# PCB-BI8-1x8S.net
KiCad netlist of a schematic drawn in EAGLE
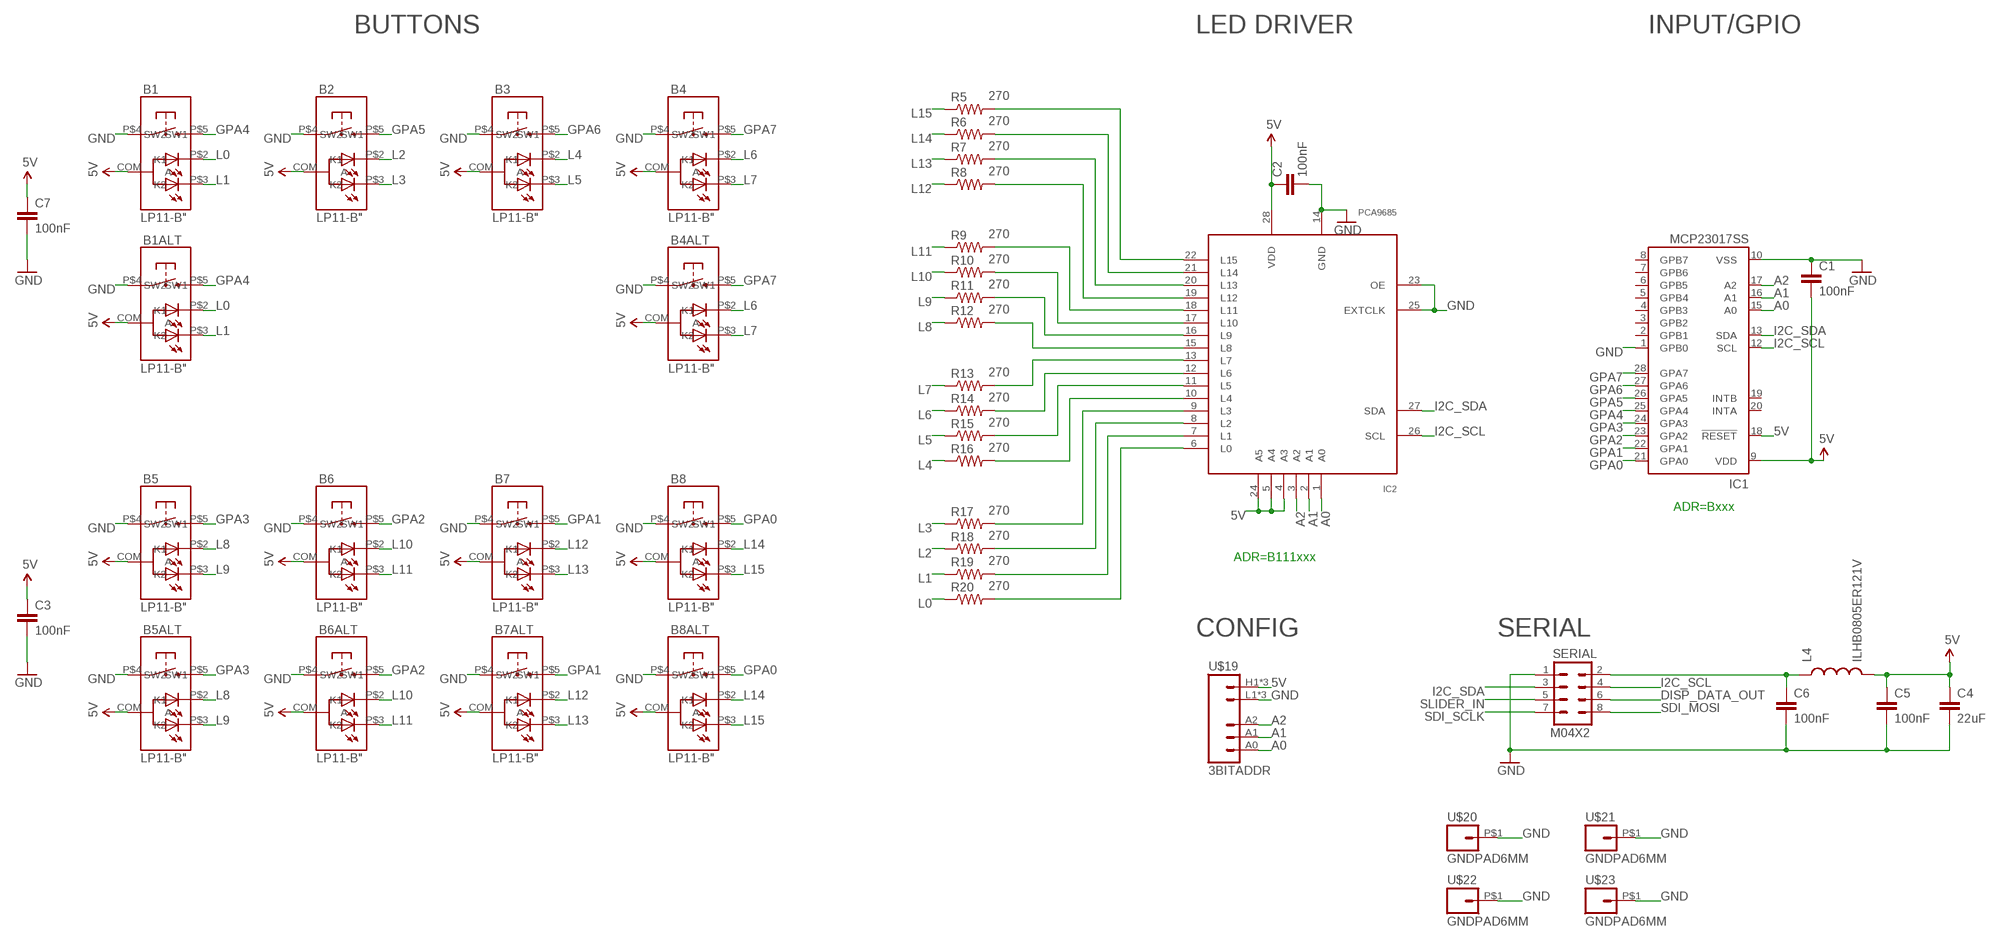
[diagram p0: schematic, sheet 1]

(export (version "E")
  (design (tool "Eeschema 10.0.6"))
  (components
    (comp (ref "B1")
      (value "LP11-B\"")
      (footprint "eagle-import:LP11")
      (libsource (lib "eagle-import") (part "LP11-B{dblquote}"))
    )
    (comp (ref "B1ALT")
      (value "LP11-B\"")
      (footprint "eagle-import:LP11")
      (libsource (lib "eagle-import") (part "LP11-B{dblquote}"))
    )
    (comp (ref "B2")
      (value "LP11-B\"")
      (footprint "eagle-import:LP11")
      (libsource (lib "eagle-import") (part "LP11-B{dblquote}"))
    )
    (comp (ref "B3")
      (value "LP11-B\"")
      (footprint "eagle-import:LP11")
      (libsource (lib "eagle-import") (part "LP11-B{dblquote}"))
    )
    (comp (ref "B4")
      (value "LP11-B\"")
      (footprint "eagle-import:LP11")
      (libsource (lib "eagle-import") (part "LP11-B{dblquote}"))
    )
    (comp (ref "B4ALT")
      (value "LP11-B\"")
      (footprint "eagle-import:LP11")
      (libsource (lib "eagle-import") (part "LP11-B{dblquote}"))
    )
    (comp (ref "B5")
      (value "LP11-B\"")
      (footprint "eagle-import:LP11")
      (libsource (lib "eagle-import") (part "LP11-B{dblquote}"))
    )
    (comp (ref "B5ALT")
      (value "LP11-B\"")
      (footprint "eagle-import:LP11")
      (libsource (lib "eagle-import") (part "LP11-B{dblquote}"))
    )
    (comp (ref "B6")
      (value "LP11-B\"")
      (footprint "eagle-import:LP11")
      (libsource (lib "eagle-import") (part "LP11-B{dblquote}"))
    )
    (comp (ref "B6ALT")
      (value "LP11-B\"")
      (footprint "eagle-import:LP11")
      (libsource (lib "eagle-import") (part "LP11-B{dblquote}"))
    )
    (comp (ref "B7")
      (value "LP11-B\"")
      (footprint "eagle-import:LP11")
      (libsource (lib "eagle-import") (part "LP11-B{dblquote}"))
    )
    (comp (ref "B7ALT")
      (value "LP11-B\"")
      (footprint "eagle-import:LP11")
      (libsource (lib "eagle-import") (part "LP11-B{dblquote}"))
    )
    (comp (ref "B8")
      (value "LP11-B\"")
      (footprint "eagle-import:LP11")
      (libsource (lib "eagle-import") (part "LP11-B{dblquote}"))
    )
    (comp (ref "B8ALT")
      (value "LP11-B\"")
      (footprint "eagle-import:LP11")
      (libsource (lib "eagle-import") (part "LP11-B{dblquote}"))
    )
    (comp (ref "C1")
      (value "100nF")
      (footprint "eagle-import:0603-CAP")
      (libsource (lib "eagle-import") (part "CAP0603-CAP"))
    )
    (comp (ref "C2")
      (value "100nF")
      (footprint "eagle-import:0603-CAP")
      (libsource (lib "eagle-import") (part "CAP0603-CAP"))
    )
    (comp (ref "C3")
      (value "100nF")
      (footprint "eagle-import:0603-CAP")
      (libsource (lib "eagle-import") (part "CAP0603-CAP"))
    )
    (comp (ref "C4")
      (value "22uF")
      (footprint "eagle-import:0805")
      (libsource (lib "eagle-import") (part "CAP0805"))
    )
    (comp (ref "C5")
      (value "100nF")
      (footprint "eagle-import:0603-CAP")
      (libsource (lib "eagle-import") (part "CAP0603-CAP"))
    )
    (comp (ref "C6")
      (value "100nF")
      (footprint "eagle-import:0603-CAP")
      (libsource (lib "eagle-import") (part "CAP0603-CAP"))
    )
    (comp (ref "C7")
      (value "100nF")
      (footprint "eagle-import:0603-CAP")
      (libsource (lib "eagle-import") (part "CAP0603-CAP"))
    )
    (comp (ref "IC1")
      (value "MCP23017SS")
      (footprint "eagle-import:SSOP28")
      (fields
        (field (name "MF") "MICROCHIP")
        (field (name "MPN") "MCP23017-E/SS")
        (field (name "MPN_1") "MCP23017-E/SS")
        (field (name "OC_FARNELL") "1467674")
        (field (name "OC_NEWARK") "31K2960")
      )
      (libsource (lib "eagle-import") (part "MCP23017SS"))
    )
    (comp (ref "IC2")
      (value "PCA9685")
      (footprint "eagle-import:TSSOP28")
      (libsource (lib "eagle-import") (part "PCA9685"))
    )
    (comp (ref "L4")
      (value "ILHB0805ER121V")
      (footprint "eagle-import:0805")
      (libsource (lib "eagle-import") (part "INDUCTOR0805"))
    )
    (comp (ref "R5")
      (value "270")
      (footprint "eagle-import:0603-RES")
      (libsource (lib "eagle-import") (part "RESISTOR0603-RES"))
    )
    (comp (ref "R6")
      (value "270")
      (footprint "eagle-import:0603-RES")
      (libsource (lib "eagle-import") (part "RESISTOR0603-RES"))
    )
    (comp (ref "R7")
      (value "270")
      (footprint "eagle-import:0603-RES")
      (libsource (lib "eagle-import") (part "RESISTOR0603-RES"))
    )
    (comp (ref "R8")
      (value "270")
      (footprint "eagle-import:0603-RES")
      (libsource (lib "eagle-import") (part "RESISTOR0603-RES"))
    )
    (comp (ref "R9")
      (value "270")
      (footprint "eagle-import:0603-RES")
      (libsource (lib "eagle-import") (part "RESISTOR0603-RES"))
    )
    (comp (ref "R10")
      (value "270")
      (footprint "eagle-import:0603-RES")
      (libsource (lib "eagle-import") (part "RESISTOR0603-RES"))
    )
    (comp (ref "R11")
      (value "270")
      (footprint "eagle-import:0603-RES")
      (libsource (lib "eagle-import") (part "RESISTOR0603-RES"))
    )
    (comp (ref "R12")
      (value "270")
      (footprint "eagle-import:0603-RES")
      (libsource (lib "eagle-import") (part "RESISTOR0603-RES"))
    )
    (comp (ref "R13")
      (value "270")
      (footprint "eagle-import:0603-RES")
      (libsource (lib "eagle-import") (part "RESISTOR0603-RES"))
    )
    (comp (ref "R14")
      (value "270")
      (footprint "eagle-import:0603-RES")
      (libsource (lib "eagle-import") (part "RESISTOR0603-RES"))
    )
    (comp (ref "R15")
      (value "270")
      (footprint "eagle-import:0603-RES")
      (libsource (lib "eagle-import") (part "RESISTOR0603-RES"))
    )
    (comp (ref "R16")
      (value "270")
      (footprint "eagle-import:0603-RES")
      (libsource (lib "eagle-import") (part "RESISTOR0603-RES"))
    )
    (comp (ref "R17")
      (value "270")
      (footprint "eagle-import:0603-RES")
      (libsource (lib "eagle-import") (part "RESISTOR0603-RES"))
    )
    (comp (ref "R18")
      (value "270")
      (footprint "eagle-import:0603-RES")
      (libsource (lib "eagle-import") (part "RESISTOR0603-RES"))
    )
    (comp (ref "R19")
      (value "270")
      (footprint "eagle-import:0603-RES")
      (libsource (lib "eagle-import") (part "RESISTOR0603-RES"))
    )
    (comp (ref "R20")
      (value "270")
      (footprint "eagle-import:0603-RES")
      (libsource (lib "eagle-import") (part "RESISTOR0603-RES"))
    )
    (comp (ref "SERIAL")
      (value "M04X2")
      (footprint "eagle-import:2X4")
      (libsource (lib "eagle-import") (part "M04X2"))
    )
    (comp (ref "U$19")
      (value "3BITADDR")
      (footprint "eagle-import:3BITADDR")
      (libsource (lib "eagle-import") (part "3BITADDR"))
    )
    (comp (ref "U$20")
      (value "GNDPAD6MM")
      (footprint "eagle-import:3.2MMPAD6MM")
      (libsource (lib "eagle-import") (part "GNDPAD6MM"))
    )
    (comp (ref "U$21")
      (value "GNDPAD6MM")
      (footprint "eagle-import:3.2MMPAD6MM")
      (libsource (lib "eagle-import") (part "GNDPAD6MM"))
    )
    (comp (ref "U$22")
      (value "GNDPAD6MM")
      (footprint "eagle-import:3.2MMPAD6MM")
      (libsource (lib "eagle-import") (part "GNDPAD6MM"))
    )
    (comp (ref "U$23")
      (value "GNDPAD6MM")
      (footprint "eagle-import:3.2MMPAD6MM")
      (libsource (lib "eagle-import") (part "GNDPAD6MM"))
    )
  )
  (nets
    (net (code "1") (name "/A0") (class "Default")
      (node (ref "IC1") (pin "15") (pinfunction "A0_15") (pintype "input"))
      (node (ref "IC2") (pin "1") (pinfunction "A0_1") (pintype "input"))
      (node (ref "U$19") (pin "A0") (pinfunction "A0_A0") (pintype "passive"))
    )
    (net (code "2") (name "/A1") (class "Default")
      (node (ref "IC1") (pin "16") (pinfunction "A1_16") (pintype "input"))
      (node (ref "IC2") (pin "2") (pinfunction "A1_2") (pintype "input"))
      (node (ref "U$19") (pin "A1") (pinfunction "A1_A1") (pintype "passive"))
    )
    (net (code "3") (name "/A2") (class "Default")
      (node (ref "IC1") (pin "17") (pinfunction "A2_17") (pintype "input"))
      (node (ref "IC2") (pin "3") (pinfunction "A2_3") (pintype "input"))
      (node (ref "U$19") (pin "A2") (pinfunction "A2_A2") (pintype "passive"))
    )
    (net (code "4") (name "/DISP_DATA_OUT") (class "Default")
      (node (ref "SERIAL") (pin "6") (pinfunction "6_6") (pintype "passive"))
    )
    (net (code "5") (name "/GPA0") (class "Default")
      (node (ref "B8") (pin "P$5") (pinfunction "SW2_P$5") (pintype "bidirectional"))
      (node (ref "B8ALT") (pin "P$5") (pinfunction "SW2_P$5") (pintype "bidirectional"))
      (node (ref "IC1") (pin "21") (pinfunction "GPA0_21") (pintype "bidirectional"))
    )
    (net (code "6") (name "/GPA1") (class "Default")
      (node (ref "B7") (pin "P$5") (pinfunction "SW2_P$5") (pintype "bidirectional"))
      (node (ref "B7ALT") (pin "P$5") (pinfunction "SW2_P$5") (pintype "bidirectional"))
      (node (ref "IC1") (pin "22") (pinfunction "GPA1_22") (pintype "bidirectional"))
    )
    (net (code "7") (name "/GPA2") (class "Default")
      (node (ref "B6") (pin "P$5") (pinfunction "SW2_P$5") (pintype "bidirectional"))
      (node (ref "B6ALT") (pin "P$5") (pinfunction "SW2_P$5") (pintype "bidirectional"))
      (node (ref "IC1") (pin "23") (pinfunction "GPA2_23") (pintype "bidirectional"))
    )
    (net (code "8") (name "/GPA3") (class "Default")
      (node (ref "B5") (pin "P$5") (pinfunction "SW2_P$5") (pintype "bidirectional"))
      (node (ref "B5ALT") (pin "P$5") (pinfunction "SW2_P$5") (pintype "bidirectional"))
      (node (ref "IC1") (pin "24") (pinfunction "GPA3_24") (pintype "bidirectional"))
    )
    (net (code "9") (name "/GPA4") (class "Default")
      (node (ref "B1") (pin "P$5") (pinfunction "SW2_P$5") (pintype "bidirectional"))
      (node (ref "B1ALT") (pin "P$5") (pinfunction "SW2_P$5") (pintype "bidirectional"))
      (node (ref "IC1") (pin "25") (pinfunction "GPA4_25") (pintype "bidirectional"))
    )
    (net (code "10") (name "/GPA5") (class "Default")
      (node (ref "B2") (pin "P$5") (pinfunction "SW2_P$5") (pintype "bidirectional"))
      (node (ref "IC1") (pin "26") (pinfunction "GPA5_26") (pintype "bidirectional"))
    )
    (net (code "11") (name "/GPA6") (class "Default")
      (node (ref "B3") (pin "P$5") (pinfunction "SW2_P$5") (pintype "bidirectional"))
      (node (ref "IC1") (pin "27") (pinfunction "GPA6_27") (pintype "bidirectional"))
    )
    (net (code "12") (name "/GPA7") (class "Default")
      (node (ref "B4") (pin "P$5") (pinfunction "SW2_P$5") (pintype "bidirectional"))
      (node (ref "B4ALT") (pin "P$5") (pinfunction "SW2_P$5") (pintype "bidirectional"))
      (node (ref "IC1") (pin "28") (pinfunction "GPA7_28") (pintype "bidirectional"))
    )
    (net (code "13") (name "/I2C_SCL") (class "Default")
      (node (ref "IC1") (pin "12") (pinfunction "SCL_12") (pintype "input"))
      (node (ref "IC2") (pin "26") (pinfunction "SCL_26") (pintype "input"))
      (node (ref "SERIAL") (pin "4") (pinfunction "4_4") (pintype "passive"))
    )
    (net (code "14") (name "/I2C_SDA") (class "Default")
      (node (ref "IC1") (pin "13") (pinfunction "SDA_13") (pintype "bidirectional"))
      (node (ref "IC2") (pin "27") (pinfunction "SDA_27") (pintype "input"))
      (node (ref "SERIAL") (pin "3") (pinfunction "3_3") (pintype "passive"))
    )
    (net (code "15") (name "/L0") (class "Default")
      (node (ref "B1") (pin "P$2") (pinfunction "K1_P$2") (pintype "bidirectional"))
      (node (ref "B1ALT") (pin "P$2") (pinfunction "K1_P$2") (pintype "bidirectional"))
      (node (ref "R20") (pin "1") (pinfunction "1_1") (pintype "passive"))
    )
    (net (code "16") (name "/L1") (class "Default")
      (node (ref "B1") (pin "P$3") (pinfunction "K2_P$3") (pintype "bidirectional"))
      (node (ref "B1ALT") (pin "P$3") (pinfunction "K2_P$3") (pintype "bidirectional"))
      (node (ref "R19") (pin "1") (pinfunction "1_1") (pintype "passive"))
    )
    (net (code "17") (name "/L2") (class "Default")
      (node (ref "B2") (pin "P$2") (pinfunction "K1_P$2") (pintype "bidirectional"))
      (node (ref "R18") (pin "1") (pinfunction "1_1") (pintype "passive"))
    )
    (net (code "18") (name "/L3") (class "Default")
      (node (ref "B2") (pin "P$3") (pinfunction "K2_P$3") (pintype "bidirectional"))
      (node (ref "R17") (pin "1") (pinfunction "1_1") (pintype "passive"))
    )
    (net (code "19") (name "/L4") (class "Default")
      (node (ref "B3") (pin "P$2") (pinfunction "K1_P$2") (pintype "bidirectional"))
      (node (ref "R16") (pin "1") (pinfunction "1_1") (pintype "passive"))
    )
    (net (code "20") (name "/L5") (class "Default")
      (node (ref "B3") (pin "P$3") (pinfunction "K2_P$3") (pintype "bidirectional"))
      (node (ref "R15") (pin "1") (pinfunction "1_1") (pintype "passive"))
    )
    (net (code "21") (name "/L6") (class "Default")
      (node (ref "B4") (pin "P$2") (pinfunction "K1_P$2") (pintype "bidirectional"))
      (node (ref "B4ALT") (pin "P$2") (pinfunction "K1_P$2") (pintype "bidirectional"))
      (node (ref "R14") (pin "1") (pinfunction "1_1") (pintype "passive"))
    )
    (net (code "22") (name "/L7") (class "Default")
      (node (ref "B4") (pin "P$3") (pinfunction "K2_P$3") (pintype "bidirectional"))
      (node (ref "B4ALT") (pin "P$3") (pinfunction "K2_P$3") (pintype "bidirectional"))
      (node (ref "R13") (pin "1") (pinfunction "1_1") (pintype "passive"))
    )
    (net (code "23") (name "/L8") (class "Default")
      (node (ref "B5") (pin "P$2") (pinfunction "K1_P$2") (pintype "bidirectional"))
      (node (ref "B5ALT") (pin "P$2") (pinfunction "K1_P$2") (pintype "bidirectional"))
      (node (ref "R12") (pin "1") (pinfunction "1_1") (pintype "passive"))
    )
    (net (code "24") (name "/L9") (class "Default")
      (node (ref "B5") (pin "P$3") (pinfunction "K2_P$3") (pintype "bidirectional"))
      (node (ref "B5ALT") (pin "P$3") (pinfunction "K2_P$3") (pintype "bidirectional"))
      (node (ref "R11") (pin "1") (pinfunction "1_1") (pintype "passive"))
    )
    (net (code "25") (name "/L10") (class "Default")
      (node (ref "B6") (pin "P$2") (pinfunction "K1_P$2") (pintype "bidirectional"))
      (node (ref "B6ALT") (pin "P$2") (pinfunction "K1_P$2") (pintype "bidirectional"))
      (node (ref "R10") (pin "1") (pinfunction "1_1") (pintype "passive"))
    )
    (net (code "26") (name "/L11") (class "Default")
      (node (ref "B6") (pin "P$3") (pinfunction "K2_P$3") (pintype "bidirectional"))
      (node (ref "B6ALT") (pin "P$3") (pinfunction "K2_P$3") (pintype "bidirectional"))
      (node (ref "R9") (pin "1") (pinfunction "1_1") (pintype "passive"))
    )
    (net (code "27") (name "/L12") (class "Default")
      (node (ref "B7") (pin "P$2") (pinfunction "K1_P$2") (pintype "bidirectional"))
      (node (ref "B7ALT") (pin "P$2") (pinfunction "K1_P$2") (pintype "bidirectional"))
      (node (ref "R8") (pin "1") (pinfunction "1_1") (pintype "passive"))
    )
    (net (code "28") (name "/L13") (class "Default")
      (node (ref "B7") (pin "P$3") (pinfunction "K2_P$3") (pintype "bidirectional"))
      (node (ref "B7ALT") (pin "P$3") (pinfunction "K2_P$3") (pintype "bidirectional"))
      (node (ref "R7") (pin "1") (pinfunction "1_1") (pintype "passive"))
    )
    (net (code "29") (name "/L14") (class "Default")
      (node (ref "B8") (pin "P$2") (pinfunction "K1_P$2") (pintype "bidirectional"))
      (node (ref "B8ALT") (pin "P$2") (pinfunction "K1_P$2") (pintype "bidirectional"))
      (node (ref "R6") (pin "1") (pinfunction "1_1") (pintype "passive"))
    )
    (net (code "30") (name "/L15") (class "Default")
      (node (ref "B8") (pin "P$3") (pinfunction "K2_P$3") (pintype "bidirectional"))
      (node (ref "B8ALT") (pin "P$3") (pinfunction "K2_P$3") (pintype "bidirectional"))
      (node (ref "R5") (pin "1") (pinfunction "1_1") (pintype "passive"))
    )
    (net (code "31") (name "/SDI_MOSI") (class "Default")
      (node (ref "SERIAL") (pin "8") (pinfunction "8_8") (pintype "passive"))
    )
    (net (code "32") (name "/SDI_SCLK") (class "Default")
      (node (ref "SERIAL") (pin "7") (pinfunction "7_7") (pintype "passive"))
    )
    (net (code "33") (name "/SLIDER_IN") (class "Default")
      (node (ref "SERIAL") (pin "5") (pinfunction "5_5") (pintype "passive"))
    )
    (net (code "34") (name "5V") (class "Default")
      (node (ref "B1") (pin "COM") (pinfunction "A_COM") (pintype "bidirectional"))
      (node (ref "B1ALT") (pin "COM") (pinfunction "A_COM") (pintype "bidirectional"))
      (node (ref "B2") (pin "COM") (pinfunction "A_COM") (pintype "bidirectional"))
      (node (ref "B3") (pin "COM") (pinfunction "A_COM") (pintype "bidirectional"))
      (node (ref "B4") (pin "COM") (pinfunction "A_COM") (pintype "bidirectional"))
      (node (ref "B4ALT") (pin "COM") (pinfunction "A_COM") (pintype "bidirectional"))
      (node (ref "B5") (pin "COM") (pinfunction "A_COM") (pintype "bidirectional"))
      (node (ref "B5ALT") (pin "COM") (pinfunction "A_COM") (pintype "bidirectional"))
      (node (ref "B6") (pin "COM") (pinfunction "A_COM") (pintype "bidirectional"))
      (node (ref "B6ALT") (pin "COM") (pinfunction "A_COM") (pintype "bidirectional"))
      (node (ref "B7") (pin "COM") (pinfunction "A_COM") (pintype "bidirectional"))
      (node (ref "B7ALT") (pin "COM") (pinfunction "A_COM") (pintype "bidirectional"))
      (node (ref "B8") (pin "COM") (pinfunction "A_COM") (pintype "bidirectional"))
      (node (ref "B8ALT") (pin "COM") (pinfunction "A_COM") (pintype "bidirectional"))
      (node (ref "C1") (pin "2") (pinfunction "2_2") (pintype "passive"))
      (node (ref "C2") (pin "1") (pinfunction "1_1") (pintype "passive"))
      (node (ref "C3") (pin "1") (pinfunction "1_1") (pintype "passive"))
      (node (ref "C4") (pin "1") (pinfunction "1_1") (pintype "passive"))
      (node (ref "C5") (pin "1") (pinfunction "1_1") (pintype "passive"))
      (node (ref "C7") (pin "1") (pinfunction "1_1") (pintype "passive"))
      (node (ref "IC1") (pin "18") (pinfunction "~{RESET}_18") (pintype "input"))
      (node (ref "IC1") (pin "9") (pinfunction "VDD_9") (pintype "power_in"))
      (node (ref "IC2") (pin "24") (pinfunction "A5_24") (pintype "input"))
      (node (ref "IC2") (pin "28") (pinfunction "VDD_28") (pintype "power_in"))
      (node (ref "IC2") (pin "4") (pinfunction "A3_4") (pintype "input"))
      (node (ref "IC2") (pin "5") (pinfunction "A4_5") (pintype "input"))
      (node (ref "L4") (pin "2") (pinfunction "2_2") (pintype "passive"))
      (node (ref "U$19") (pin "H1") (pinfunction "VCC_H1") (pintype "passive"))
      (node (ref "U$19") (pin "H2") (pinfunction "VCC_H2") (pintype "passive"))
      (node (ref "U$19") (pin "H3") (pinfunction "VCC_H3") (pintype "passive"))
    )
    (net (code "35") (name "GND") (class "Default")
      (node (ref "B1") (pin "P$4") (pinfunction "SW1_P$4") (pintype "bidirectional"))
      (node (ref "B1ALT") (pin "P$4") (pinfunction "SW1_P$4") (pintype "bidirectional"))
      (node (ref "B2") (pin "P$4") (pinfunction "SW1_P$4") (pintype "bidirectional"))
      (node (ref "B3") (pin "P$4") (pinfunction "SW1_P$4") (pintype "bidirectional"))
      (node (ref "B4") (pin "P$4") (pinfunction "SW1_P$4") (pintype "bidirectional"))
      (node (ref "B4ALT") (pin "P$4") (pinfunction "SW1_P$4") (pintype "bidirectional"))
      (node (ref "B5") (pin "P$4") (pinfunction "SW1_P$4") (pintype "bidirectional"))
      (node (ref "B5ALT") (pin "P$4") (pinfunction "SW1_P$4") (pintype "bidirectional"))
      (node (ref "B6") (pin "P$4") (pinfunction "SW1_P$4") (pintype "bidirectional"))
      (node (ref "B6ALT") (pin "P$4") (pinfunction "SW1_P$4") (pintype "bidirectional"))
      (node (ref "B7") (pin "P$4") (pinfunction "SW1_P$4") (pintype "bidirectional"))
      (node (ref "B7ALT") (pin "P$4") (pinfunction "SW1_P$4") (pintype "bidirectional"))
      (node (ref "B8") (pin "P$4") (pinfunction "SW1_P$4") (pintype "bidirectional"))
      (node (ref "B8ALT") (pin "P$4") (pinfunction "SW1_P$4") (pintype "bidirectional"))
      (node (ref "C1") (pin "1") (pinfunction "1_1") (pintype "passive"))
      (node (ref "C2") (pin "2") (pinfunction "2_2") (pintype "passive"))
      (node (ref "C3") (pin "2") (pinfunction "2_2") (pintype "passive"))
      (node (ref "C4") (pin "2") (pinfunction "2_2") (pintype "passive"))
      (node (ref "C5") (pin "2") (pinfunction "2_2") (pintype "passive"))
      (node (ref "C6") (pin "2") (pinfunction "2_2") (pintype "passive"))
      (node (ref "C7") (pin "2") (pinfunction "2_2") (pintype "passive"))
      (node (ref "IC1") (pin "1") (pinfunction "GPB0_1") (pintype "bidirectional"))
      (node (ref "IC1") (pin "10") (pinfunction "VSS_10") (pintype "power_in"))
      (node (ref "IC2") (pin "14") (pinfunction "GND_14") (pintype "power_in"))
      (node (ref "IC2") (pin "23") (pinfunction "OE_23") (pintype "input"))
      (node (ref "IC2") (pin "25") (pinfunction "EXTCLK_25") (pintype "input"))
      (node (ref "SERIAL") (pin "1") (pinfunction "1_1") (pintype "passive"))
      (node (ref "U$19") (pin "L1") (pinfunction "GND_L1") (pintype "passive"))
      (node (ref "U$19") (pin "L2") (pinfunction "GND_L2") (pintype "passive"))
      (node (ref "U$19") (pin "L3") (pinfunction "GND_L3") (pintype "passive"))
      (node (ref "U$20") (pin "P$1") (pinfunction "1_P$1") (pintype "passive"))
      (node (ref "U$21") (pin "P$1") (pinfunction "1_P$1") (pintype "passive"))
      (node (ref "U$22") (pin "P$1") (pinfunction "1_P$1") (pintype "passive"))
      (node (ref "U$23") (pin "P$1") (pinfunction "1_P$1") (pintype "passive"))
    )
    (net (code "36") (name "Net-(C6-Pad1)") (class "Default")
      (node (ref "C6") (pin "1") (pinfunction "1_1") (pintype "passive"))
      (node (ref "L4") (pin "1") (pinfunction "1_1") (pintype "passive"))
      (node (ref "SERIAL") (pin "2") (pinfunction "2_2") (pintype "passive"))
    )
    (net (code "37") (name "Net-(IC2-L0)") (class "Default")
      (node (ref "IC2") (pin "6") (pinfunction "L0_6") (pintype "output"))
      (node (ref "R20") (pin "2") (pinfunction "2_2") (pintype "passive"))
    )
    (net (code "38") (name "Net-(IC2-L1)") (class "Default")
      (node (ref "IC2") (pin "7") (pinfunction "L1_7") (pintype "output"))
      (node (ref "R19") (pin "2") (pinfunction "2_2") (pintype "passive"))
    )
    (net (code "39") (name "Net-(IC2-L2)") (class "Default")
      (node (ref "IC2") (pin "8") (pinfunction "L2_8") (pintype "output"))
      (node (ref "R18") (pin "2") (pinfunction "2_2") (pintype "passive"))
    )
    (net (code "40") (name "Net-(IC2-L3)") (class "Default")
      (node (ref "IC2") (pin "9") (pinfunction "L3_9") (pintype "output"))
      (node (ref "R17") (pin "2") (pinfunction "2_2") (pintype "passive"))
    )
    (net (code "41") (name "Net-(IC2-L4)") (class "Default")
      (node (ref "IC2") (pin "10") (pinfunction "L4_10") (pintype "output"))
      (node (ref "R16") (pin "2") (pinfunction "2_2") (pintype "passive"))
    )
    (net (code "42") (name "Net-(IC2-L5)") (class "Default")
      (node (ref "IC2") (pin "11") (pinfunction "L5_11") (pintype "output"))
      (node (ref "R15") (pin "2") (pinfunction "2_2") (pintype "passive"))
    )
    (net (code "43") (name "Net-(IC2-L6)") (class "Default")
      (node (ref "IC2") (pin "12") (pinfunction "L6_12") (pintype "output"))
      (node (ref "R14") (pin "2") (pinfunction "2_2") (pintype "passive"))
    )
    (net (code "44") (name "Net-(IC2-L7)") (class "Default")
      (node (ref "IC2") (pin "13") (pinfunction "L7_13") (pintype "output"))
      (node (ref "R13") (pin "2") (pinfunction "2_2") (pintype "passive"))
    )
    (net (code "45") (name "Net-(IC2-L8)") (class "Default")
      (node (ref "IC2") (pin "15") (pinfunction "L8_15") (pintype "output"))
      (node (ref "R12") (pin "2") (pinfunction "2_2") (pintype "passive"))
    )
    (net (code "46") (name "Net-(IC2-L9)") (class "Default")
      (node (ref "IC2") (pin "16") (pinfunction "L9_16") (pintype "output"))
      (node (ref "R11") (pin "2") (pinfunction "2_2") (pintype "passive"))
    )
    (net (code "47") (name "Net-(IC2-L10)") (class "Default")
      (node (ref "IC2") (pin "17") (pinfunction "L10_17") (pintype "output"))
      (node (ref "R10") (pin "2") (pinfunction "2_2") (pintype "passive"))
    )
    (net (code "48") (name "Net-(IC2-L11)") (class "Default")
      (node (ref "IC2") (pin "18") (pinfunction "L11_18") (pintype "output"))
      (node (ref "R9") (pin "2") (pinfunction "2_2") (pintype "passive"))
    )
    (net (code "49") (name "Net-(IC2-L12)") (class "Default")
      (node (ref "IC2") (pin "19") (pinfunction "L12_19") (pintype "output"))
      (node (ref "R8") (pin "2") (pinfunction "2_2") (pintype "passive"))
    )
    (net (code "50") (name "Net-(IC2-L13)") (class "Default")
      (node (ref "IC2") (pin "20") (pinfunction "L13_20") (pintype "output"))
      (node (ref "R7") (pin "2") (pinfunction "2_2") (pintype "passive"))
    )
    (net (code "51") (name "Net-(IC2-L14)") (class "Default")
      (node (ref "IC2") (pin "21") (pinfunction "L14_21") (pintype "output"))
      (node (ref "R6") (pin "2") (pinfunction "2_2") (pintype "passive"))
    )
    (net (code "52") (name "Net-(IC2-L15)") (class "Default")
      (node (ref "IC2") (pin "22") (pinfunction "L15_22") (pintype "output"))
      (node (ref "R5") (pin "2") (pinfunction "2_2") (pintype "passive"))
    )
    (net (code "53") (name "unconnected-(IC1-GPB1-Pad2)") (class "Default")
      (node (ref "IC1") (pin "2") (pinfunction "GPB1_2") (pintype "bidirectional"))
    )
    (net (code "54") (name "unconnected-(IC1-GPB2-Pad3)") (class "Default")
      (node (ref "IC1") (pin "3") (pinfunction "GPB2_3") (pintype "bidirectional"))
    )
    (net (code "55") (name "unconnected-(IC1-GPB3-Pad4)") (class "Default")
      (node (ref "IC1") (pin "4") (pinfunction "GPB3_4") (pintype "bidirectional"))
    )
    (net (code "56") (name "unconnected-(IC1-GPB4-Pad5)") (class "Default")
      (node (ref "IC1") (pin "5") (pinfunction "GPB4_5") (pintype "bidirectional"))
    )
    (net (code "57") (name "unconnected-(IC1-GPB5-Pad6)") (class "Default")
      (node (ref "IC1") (pin "6") (pinfunction "GPB5_6") (pintype "bidirectional"))
    )
    (net (code "58") (name "unconnected-(IC1-GPB6-Pad7)") (class "Default")
      (node (ref "IC1") (pin "7") (pinfunction "GPB6_7") (pintype "bidirectional"))
    )
    (net (code "59") (name "unconnected-(IC1-GPB7-Pad8)") (class "Default")
      (node (ref "IC1") (pin "8") (pinfunction "GPB7_8") (pintype "bidirectional"))
    )
    (net (code "60") (name "unconnected-(IC1-INTA-Pad20)") (class "Default")
      (node (ref "IC1") (pin "20") (pinfunction "INTA_20") (pintype "output"))
    )
    (net (code "61") (name "unconnected-(IC1-INTB-Pad19)") (class "Default")
      (node (ref "IC1") (pin "19") (pinfunction "INTB_19") (pintype "output"))
    )
  )
)
